# Flodar_Board_V1-1.net
KiCad netlist of a schematic drawn in EAGLE
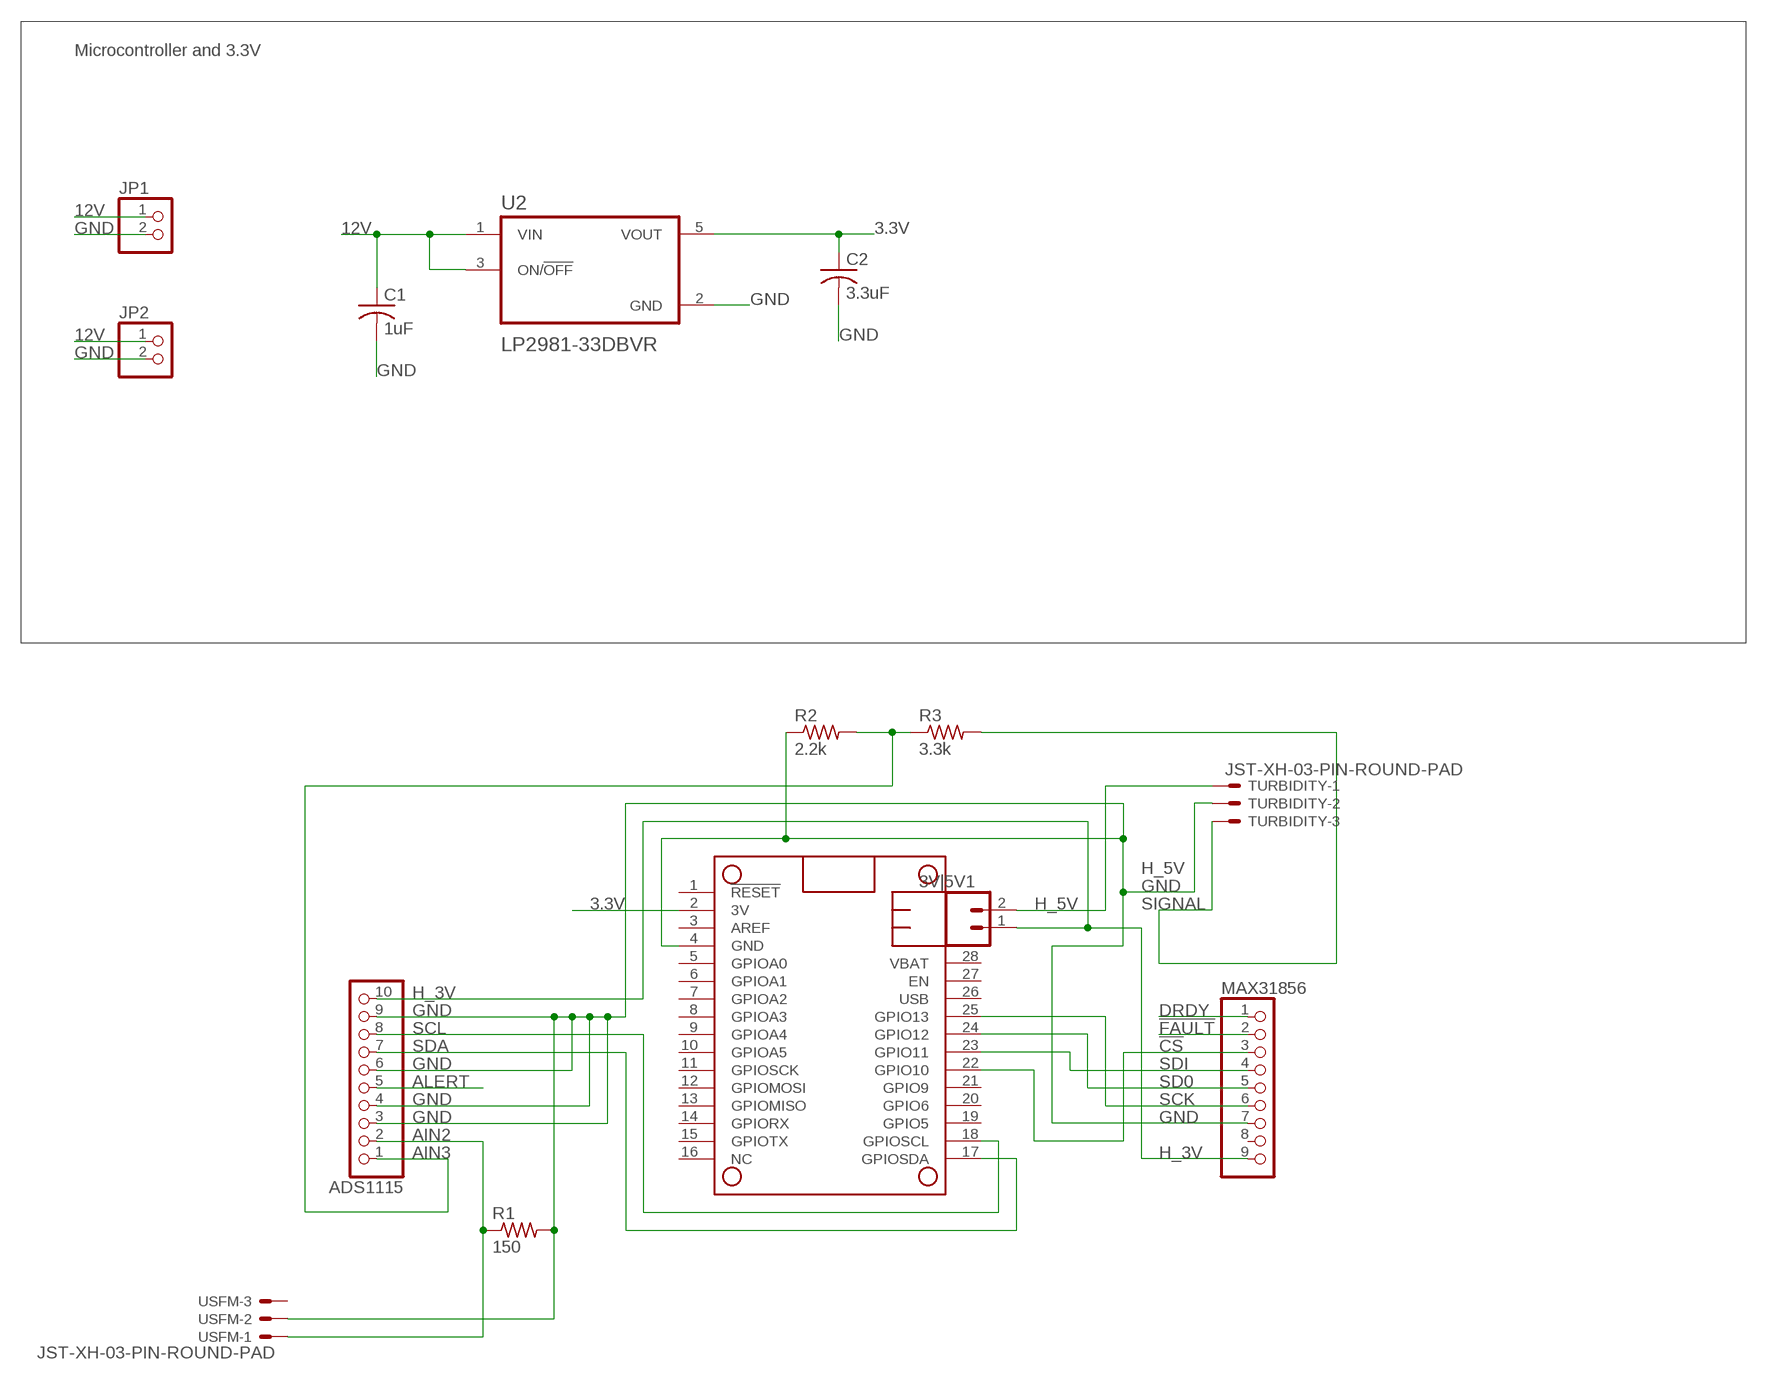
[diagram p0: schematic, sheet 1]

(export (version "E")
  (design (tool "Eeschema 10.0.6"))
  (components
    (comp (ref "3V|5V1")
      (value "CONN_021X02_NO_SILK")
      (footprint "eagle-import:1X02_NO_SILK")
      (libsource (lib "eagle-import") (part "CONN_021X02_NO_SILK"))
    )
    (comp (ref "ADS1115")
      (value "HEADER-1X1070MIL")
      (footprint "eagle-import:1X10_ROUND70")
      (libsource (lib "eagle-import") (part "HEADER-1X1070MIL"))
    )
    (comp (ref "C1")
      (value "1uF")
      (footprint "eagle-import:C1206")
      (libsource (lib "eagle-import") (part "C-USC1206"))
    )
    (comp (ref "C2")
      (value "3.3uF")
      (footprint "eagle-import:C1206")
      (libsource (lib "eagle-import") (part "C-USC1206"))
    )
    (comp (ref "JP1")
      (value "PINHD-1X2")
      (footprint "eagle-import:1X02")
      (libsource (lib "eagle-import") (part "PINHD-1X2"))
    )
    (comp (ref "JP2")
      (value "PINHD-1X2")
      (footprint "eagle-import:1X02")
      (libsource (lib "eagle-import") (part "PINHD-1X2"))
    )
    (comp (ref "MAX31856")
      (value "HEADER-1X970MIL")
      (footprint "eagle-import:1X09_ROUND_70")
      (libsource (lib "eagle-import") (part "HEADER-1X970MIL"))
    )
    (comp (ref "MS3")
      (value "FEATHERWING")
      (footprint "eagle-import:FEATHERWING")
      (libsource (lib "eagle-import") (part "FEATHERWING"))
    )
    (comp (ref "R1")
      (value "150")
      (footprint "eagle-import:R1206")
      (libsource (lib "eagle-import") (part "R-US_R1206"))
    )
    (comp (ref "R2")
      (value "2.2k")
      (footprint "eagle-import:R1206")
      (libsource (lib "eagle-import") (part "R-US_R1206"))
    )
    (comp (ref "R3")
      (value "3.3k")
      (footprint "eagle-import:R1206")
      (libsource (lib "eagle-import") (part "R-US_R1206"))
    )
    (comp (ref "TURBIDITY")
      (value "JST-XH-03-PIN-ROUND-PAD")
      (footprint "eagle-import:JST-XH-03-PACKAGE-ROUND-PAD")
      (libsource (lib "eagle-import") (part "JST-XH-03-PIN-ROUND-PAD"))
    )
    (comp (ref "U2")
      (value "LP2981-33DBVR")
      (footprint "eagle-import:SOT95P280X145-5N")
      (fields (field (name "MF") "Texas Instruments") (field (name "MP") "LP2981-50DBVR"))
      (libsource (lib "eagle-import") (part "LP2981-50DBVR"))
    )
    (comp (ref "USFM")
      (value "JST-XH-03-PIN-ROUND-PAD")
      (footprint "eagle-import:JST-XH-03-PACKAGE-ROUND-PAD")
      (libsource (lib "eagle-import") (part "JST-XH-03-PIN-ROUND-PAD"))
    )
  )
  (nets
    (net (code "1") (name "/3.3V") (class "Default")
      (node (ref "C2") (pin "1") (pinfunction "1_1") (pintype "passive"))
      (node (ref "MS3") (pin "2") (pinfunction "3V_2") (pintype "power_in"))
      (node (ref "U2") (pin "5") (pinfunction "VOUT_5") (pintype "output"))
    )
    (net (code "2") (name "/12V") (class "Default")
      (node (ref "C1") (pin "1") (pinfunction "1_1") (pintype "passive"))
      (node (ref "JP1") (pin "1") (pinfunction "1_1") (pintype "passive"))
      (node (ref "JP2") (pin "1") (pinfunction "1_1") (pintype "passive"))
      (node (ref "U2") (pin "1") (pinfunction "VIN_1") (pintype "input"))
      (node (ref "U2") (pin "3") (pinfunction "ON/~{OFF}_3") (pintype "bidirectional"))
    )
    (net (code "3") (name "/AIN2") (class "Default")
      (node (ref "ADS1115") (pin "2") (pinfunction "2_2") (pintype "passive"))
      (node (ref "R1") (pin "1") (pinfunction "1_1") (pintype "passive"))
      (node (ref "USFM") (pin "1") (pinfunction "S_1") (pintype "passive"))
    )
    (net (code "4") (name "/AIN3") (class "Default")
      (node (ref "ADS1115") (pin "1") (pinfunction "1_1") (pintype "passive"))
      (node (ref "R2") (pin "2") (pinfunction "2_2") (pintype "passive"))
      (node (ref "R3") (pin "1") (pinfunction "1_1") (pintype "passive"))
    )
    (net (code "5") (name "/ALERT") (class "Default")
      (node (ref "ADS1115") (pin "5") (pinfunction "5_5") (pintype "passive"))
    )
    (net (code "6") (name "/DRDY") (class "Default")
      (node (ref "MAX31856") (pin "1") (pinfunction "1_1") (pintype "passive"))
    )
    (net (code "7") (name "/GND") (class "Default")
      (node (ref "ADS1115") (pin "3") (pinfunction "3_3") (pintype "passive"))
      (node (ref "ADS1115") (pin "4") (pinfunction "4_4") (pintype "passive"))
      (node (ref "ADS1115") (pin "6") (pinfunction "6_6") (pintype "passive"))
      (node (ref "ADS1115") (pin "9") (pinfunction "9_9") (pintype "passive"))
      (node (ref "C1") (pin "2") (pinfunction "2_2") (pintype "passive"))
      (node (ref "C2") (pin "2") (pinfunction "2_2") (pintype "passive"))
      (node (ref "JP1") (pin "2") (pinfunction "2_2") (pintype "passive"))
      (node (ref "JP2") (pin "2") (pinfunction "2_2") (pintype "passive"))
      (node (ref "MAX31856") (pin "7") (pinfunction "7_7") (pintype "passive"))
      (node (ref "MS3") (pin "4") (pinfunction "GND_4") (pintype "power_in"))
      (node (ref "R1") (pin "2") (pinfunction "2_2") (pintype "passive"))
      (node (ref "R2") (pin "1") (pinfunction "1_1") (pintype "passive"))
      (node (ref "TURBIDITY") (pin "2") (pinfunction "S_2") (pintype "passive"))
      (node (ref "U2") (pin "2") (pinfunction "GND_2") (pintype "power_in"))
      (node (ref "USFM") (pin "2") (pinfunction "S_2") (pintype "passive"))
    )
    (net (code "8") (name "/H_3V") (class "Default")
      (node (ref "3V|5V1") (pin "1") (pinfunction "1_1") (pintype "passive"))
      (node (ref "ADS1115") (pin "10") (pinfunction "10_10") (pintype "passive"))
      (node (ref "MAX31856") (pin "9") (pinfunction "9_9") (pintype "passive"))
    )
    (net (code "9") (name "/H_5V") (class "Default")
      (node (ref "3V|5V1") (pin "2") (pinfunction "2_2") (pintype "passive"))
      (node (ref "TURBIDITY") (pin "1") (pinfunction "S_1") (pintype "passive"))
    )
    (net (code "10") (name "/SCK") (class "Default")
      (node (ref "MAX31856") (pin "6") (pinfunction "6_6") (pintype "passive"))
      (node (ref "MS3") (pin "25") (pinfunction "GPIO13_25") (pintype "bidirectional"))
    )
    (net (code "11") (name "/SCL") (class "Default")
      (node (ref "ADS1115") (pin "8") (pinfunction "8_8") (pintype "passive"))
      (node (ref "MS3") (pin "18") (pinfunction "GPIOSCL_18") (pintype "bidirectional"))
    )
    (net (code "12") (name "/SD0") (class "Default")
      (node (ref "MAX31856") (pin "5") (pinfunction "5_5") (pintype "passive"))
      (node (ref "MS3") (pin "24") (pinfunction "GPIO12_24") (pintype "bidirectional"))
    )
    (net (code "13") (name "/SDA") (class "Default")
      (node (ref "ADS1115") (pin "7") (pinfunction "7_7") (pintype "passive"))
      (node (ref "MS3") (pin "17") (pinfunction "GPIOSDA_17") (pintype "bidirectional"))
    )
    (net (code "14") (name "/SDI") (class "Default")
      (node (ref "MAX31856") (pin "4") (pinfunction "4_4") (pintype "passive"))
      (node (ref "MS3") (pin "23") (pinfunction "GPIO11_23") (pintype "bidirectional"))
    )
    (net (code "15") (name "/SIGNAL") (class "Default")
      (node (ref "R3") (pin "2") (pinfunction "2_2") (pintype "passive"))
      (node (ref "TURBIDITY") (pin "3") (pinfunction "S_3") (pintype "passive"))
    )
    (net (code "16") (name "/USB") (class "Default")
      (node (ref "MS3") (pin "26") (pinfunction "USB_26") (pintype "power_in"))
    )
    (net (code "17") (name "/VBAT") (class "Default")
      (node (ref "MS3") (pin "28") (pinfunction "VBAT_28") (pintype "power_in"))
    )
    (net (code "18") (name "/~{CS}") (class "Default")
      (node (ref "MAX31856") (pin "3") (pinfunction "3_3") (pintype "passive"))
      (node (ref "MS3") (pin "22") (pinfunction "GPIO10_22") (pintype "bidirectional"))
    )
    (net (code "19") (name "/~{FAULT}") (class "Default")
      (node (ref "MAX31856") (pin "2") (pinfunction "2_2") (pintype "passive"))
    )
    (net (code "20") (name "unconnected-(MAX31856-Pad8)") (class "Default")
      (node (ref "MAX31856") (pin "8") (pinfunction "8_8") (pintype "passive"))
    )
    (net (code "21") (name "unconnected-(MS3-AREF-Pad3)") (class "Default")
      (node (ref "MS3") (pin "3") (pinfunction "AREF_3") (pintype "passive"))
    )
    (net (code "22") (name "unconnected-(MS3-EN-Pad27)") (class "Default")
      (node (ref "MS3") (pin "27") (pinfunction "EN_27") (pintype "passive"))
    )
    (net (code "23") (name "unconnected-(MS3-GPIO5-Pad19)") (class "Default")
      (node (ref "MS3") (pin "19") (pinfunction "GPIO5_19") (pintype "bidirectional"))
    )
    (net (code "24") (name "unconnected-(MS3-GPIO6-Pad20)") (class "Default")
      (node (ref "MS3") (pin "20") (pinfunction "GPIO6_20") (pintype "bidirectional"))
    )
    (net (code "25") (name "unconnected-(MS3-GPIO9-Pad21)") (class "Default")
      (node (ref "MS3") (pin "21") (pinfunction "GPIO9_21") (pintype "bidirectional"))
    )
    (net (code "26") (name "unconnected-(MS3-GPIOA0-Pad5)") (class "Default")
      (node (ref "MS3") (pin "5") (pinfunction "GPIOA0_5") (pintype "bidirectional"))
    )
    (net (code "27") (name "unconnected-(MS3-GPIOA1-Pad6)") (class "Default")
      (node (ref "MS3") (pin "6") (pinfunction "GPIOA1_6") (pintype "bidirectional"))
    )
    (net (code "28") (name "unconnected-(MS3-GPIOA2-Pad7)") (class "Default")
      (node (ref "MS3") (pin "7") (pinfunction "GPIOA2_7") (pintype "bidirectional"))
    )
    (net (code "29") (name "unconnected-(MS3-GPIOA3-Pad8)") (class "Default")
      (node (ref "MS3") (pin "8") (pinfunction "GPIOA3_8") (pintype "bidirectional"))
    )
    (net (code "30") (name "unconnected-(MS3-GPIOA4-Pad9)") (class "Default")
      (node (ref "MS3") (pin "9") (pinfunction "GPIOA4_9") (pintype "bidirectional"))
    )
    (net (code "31") (name "unconnected-(MS3-GPIOA5-Pad10)") (class "Default")
      (node (ref "MS3") (pin "10") (pinfunction "GPIOA5_10") (pintype "bidirectional"))
    )
    (net (code "32") (name "unconnected-(MS3-GPIOMISO-Pad13)") (class "Default")
      (node (ref "MS3") (pin "13") (pinfunction "GPIOMISO_13") (pintype "bidirectional"))
    )
    (net (code "33") (name "unconnected-(MS3-GPIOMOSI-Pad12)") (class "Default")
      (node (ref "MS3") (pin "12") (pinfunction "GPIOMOSI_12") (pintype "bidirectional"))
    )
    (net (code "34") (name "unconnected-(MS3-GPIORX-Pad14)") (class "Default")
      (node (ref "MS3") (pin "14") (pinfunction "GPIORX_14") (pintype "bidirectional"))
    )
    (net (code "35") (name "unconnected-(MS3-GPIOSCK-Pad11)") (class "Default")
      (node (ref "MS3") (pin "11") (pinfunction "GPIOSCK_11") (pintype "bidirectional"))
    )
    (net (code "36") (name "unconnected-(MS3-GPIOTX-Pad15)") (class "Default")
      (node (ref "MS3") (pin "15") (pinfunction "GPIOTX_15") (pintype "bidirectional"))
    )
    (net (code "37") (name "unconnected-(MS3-NC-Pad16)") (class "Default")
      (node (ref "MS3") (pin "16") (pinfunction "NC_16") (pintype "passive"))
    )
    (net (code "38") (name "unconnected-(MS3-~{RESET}-Pad1)") (class "Default")
      (node (ref "MS3") (pin "1") (pinfunction "~{RESET}_1") (pintype "input"))
    )
    (net (code "39") (name "unconnected-(USFMC-S-Pad3)") (class "Default")
      (node (ref "USFM") (pin "3") (pinfunction "S_3") (pintype "passive"))
    )
  )
)
